# 3V3_LDO.net
KiCad netlist of a schematic drawn in Altium Designer
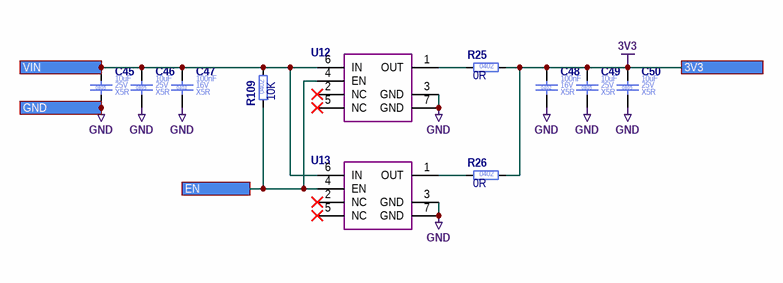
[diagram p0: 3V3_LDO.SchDoc]

(export (version "E")
  (design (tool "Eeschema 10.0.6"))
  (components
    (comp (ref "C45")
      (value "C_10UF_25V_X5R_0805_10")
      (footprint "C_0805_2012")
      (description "Ceramic Capacitor")
      (fields
        (field (name "CASE/PACKAGE") "0805")
        (field (name "VOLTAGE RATING (DC)") "25V")
        (field (name "DIELECTRIC") "X5R")
        (field (name "CAPACITANCE") "10uF")
        (field (name "TOLERANCE") "10%")
        (field (name "MANUFACTURER PART NUMBER") "CL21A106KAYNNNE")
      )
      (libsource (lib "7Sigma") (part "C"))
    )
    (comp (ref "C46")
      (value "C_10UF_25V_X5R_0805_10")
      (footprint "C_0805_2012")
      (description "Ceramic Capacitor")
      (fields
        (field (name "CASE/PACKAGE") "0805")
        (field (name "VOLTAGE RATING (DC)") "25V")
        (field (name "DIELECTRIC") "X5R")
        (field (name "CAPACITANCE") "10uF")
        (field (name "TOLERANCE") "10%")
        (field (name "MANUFACTURER PART NUMBER") "CL21A106KAYNNNE")
      )
      (libsource (lib "7Sigma") (part "C"))
    )
    (comp (ref "C47")
      (value "C_100NF_16V_X5R_0402_10")
      (footprint "C_0402_1005")
      (description "Ceramic Capacitor")
      (fields
        (field (name "CASE/PACKAGE") "0402")
        (field (name "VOLTAGE RATING (DC)") "16V")
        (field (name "DIELECTRIC") "X5R")
        (field (name "CAPACITANCE") "100nF")
        (field (name "TOLERANCE") "10%")
        (field (name "MANUFACTURER PART NUMBER") "EMK105BJ104KV-F")
      )
      (libsource (lib "7Sigma") (part "C"))
    )
    (comp (ref "C48")
      (value "C_100NF_16V_X5R_0402_10")
      (footprint "C_0402_1005")
      (description "Ceramic Capacitor")
      (fields
        (field (name "CASE/PACKAGE") "0402")
        (field (name "VOLTAGE RATING (DC)") "16V")
        (field (name "DIELECTRIC") "X5R")
        (field (name "CAPACITANCE") "100nF")
        (field (name "TOLERANCE") "10%")
        (field (name "MANUFACTURER PART NUMBER") "EMK105BJ104KV-F")
      )
      (libsource (lib "7Sigma") (part "C"))
    )
    (comp (ref "C49")
      (value "C_10UF_25V_X5R_0805_10")
      (footprint "C_0805_2012")
      (description "Ceramic Capacitor")
      (fields
        (field (name "CASE/PACKAGE") "0805")
        (field (name "VOLTAGE RATING (DC)") "25V")
        (field (name "DIELECTRIC") "X5R")
        (field (name "CAPACITANCE") "10uF")
        (field (name "TOLERANCE") "10%")
        (field (name "MANUFACTURER PART NUMBER") "CL21A106KAYNNNE")
      )
      (libsource (lib "7Sigma") (part "C"))
    )
    (comp (ref "C50")
      (value "C_10UF_25V_X5R_0805_10")
      (footprint "C_0805_2012")
      (description "Ceramic Capacitor")
      (fields
        (field (name "CASE/PACKAGE") "0805")
        (field (name "VOLTAGE RATING (DC)") "25V")
        (field (name "DIELECTRIC") "X5R")
        (field (name "CAPACITANCE") "10uF")
        (field (name "TOLERANCE") "10%")
        (field (name "MANUFACTURER PART NUMBER") "CL21A106KAYNNNE")
      )
      (libsource (lib "7Sigma") (part "C"))
    )
    (comp (ref "R25")
      (value "R_0R_0402_1")
      (footprint "R_0402_1005")
      (description "Thick Film Resistor")
      (fields
        (field (name "RESISTANCE") "0R")
        (field (name "CASE/PACKAGE") "0402")
        (field (name "TOLERANCE") "1%")
        (field (name "MANUFACTURER") "Yageo")
      )
      (libsource (lib "7Sigma") (part "R"))
    )
    (comp (ref "R26")
      (value "R_0R_0402_1")
      (footprint "R_0402_1005")
      (description "Thick Film Resistor")
      (fields
        (field (name "RESISTANCE") "0R")
        (field (name "CASE/PACKAGE") "0402")
        (field (name "TOLERANCE") "1%")
        (field (name "MANUFACTURER") "Yageo")
      )
      (libsource (lib "7Sigma") (part "R"))
    )
    (comp (ref "R109")
      (value "R_10K_0402_1")
      (footprint "R_0402_1005")
      (description "Thick Film Resistor")
      (fields
        (field (name "RESISTANCE") "10K")
        (field (name "CASE/PACKAGE") "0402")
        (field (name "TOLERANCE") "1%")
        (field (name "MANUFACTURER") "Yageo")
      )
      (libsource (lib "7Sigma") (part "R"))
    )
    (comp (ref "U12")
      (value "NCV8705MT33TCG")
      (footprint "WDFN6")
      (description "Low Dropout, Ultra-Low Iq, High PSRR, Ultra-Low Noise 3.3V")
      (fields (field (name "MANUFACTURER") "ON Semiconductor"))
      (libsource (lib "7Sigma") (part "NCV8705MT33TCG"))
    )
    (comp (ref "U13")
      (value "NCV8705MT33TCG")
      (footprint "WDFN6")
      (description "Low Dropout, Ultra-Low Iq, High PSRR, Ultra-Low Noise 3.3V")
      (fields (field (name "MANUFACTURER") "ON Semiconductor"))
      (libsource (lib "7Sigma") (part "NCV8705MT33TCG"))
    )
  )
  (nets
    (net (code "1") (name "/EN") (class "Default")
      (node (ref "R109") (pin "1") (pinfunction "1_1") (pintype "passive"))
      (node (ref "U12") (pin "4") (pinfunction "EN_4") (pintype "passive"))
      (node (ref "U13") (pin "4") (pinfunction "EN_4") (pintype "passive"))
    )
    (net (code "2") (name "/VIN") (class "Default")
      (node (ref "C45") (pin "1") (pinfunction "1_1") (pintype "passive"))
      (node (ref "C46") (pin "1") (pinfunction "1_1") (pintype "passive"))
      (node (ref "C47") (pin "1") (pinfunction "1_1") (pintype "passive"))
      (node (ref "R109") (pin "2") (pinfunction "2_2") (pintype "passive"))
      (node (ref "U12") (pin "6") (pinfunction "IN_6") (pintype "passive"))
      (node (ref "U13") (pin "6") (pinfunction "IN_6") (pintype "passive"))
    )
    (net (code "3") (name "3V3") (class "Default")
      (node (ref "C48") (pin "1") (pinfunction "1_1") (pintype "passive"))
      (node (ref "C49") (pin "1") (pinfunction "1_1") (pintype "passive"))
      (node (ref "C50") (pin "1") (pinfunction "1_1") (pintype "passive"))
      (node (ref "R25") (pin "2") (pinfunction "2_2") (pintype "passive"))
      (node (ref "R26") (pin "2") (pinfunction "2_2") (pintype "passive"))
    )
    (net (code "4") (name "GND") (class "Default")
      (node (ref "C45") (pin "2") (pinfunction "2_2") (pintype "passive"))
      (node (ref "C46") (pin "2") (pinfunction "2_2") (pintype "passive"))
      (node (ref "C47") (pin "2") (pinfunction "2_2") (pintype "passive"))
      (node (ref "C48") (pin "2") (pinfunction "2_2") (pintype "passive"))
      (node (ref "C49") (pin "2") (pinfunction "2_2") (pintype "passive"))
      (node (ref "C50") (pin "2") (pinfunction "2_2") (pintype "passive"))
      (node (ref "U12") (pin "3") (pinfunction "GND_3") (pintype "passive"))
      (node (ref "U12") (pin "7") (pinfunction "GND_7") (pintype "passive"))
      (node (ref "U13") (pin "3") (pinfunction "GND_3") (pintype "passive"))
      (node (ref "U13") (pin "7") (pinfunction "GND_7") (pintype "passive"))
    )
    (net (code "5") (name "Net-(U12-OUT)") (class "Default")
      (node (ref "R25") (pin "1") (pinfunction "1_1") (pintype "passive"))
      (node (ref "U12") (pin "1") (pinfunction "OUT_1") (pintype "passive"))
    )
    (net (code "6") (name "Net-(U13-OUT)") (class "Default")
      (node (ref "R26") (pin "1") (pinfunction "1_1") (pintype "passive"))
      (node (ref "U13") (pin "1") (pinfunction "OUT_1") (pintype "passive"))
    )
    (net (code "7") (name "unconnected-(U12-NC-Pad2)") (class "Default")
      (node (ref "U12") (pin "2") (pinfunction "NC_2") (pintype "passive+no_connect"))
    )
    (net (code "8") (name "unconnected-(U12-NC-Pad5)") (class "Default")
      (node (ref "U12") (pin "5") (pinfunction "NC_5") (pintype "passive+no_connect"))
    )
    (net (code "9") (name "unconnected-(U13-NC-Pad2)") (class "Default")
      (node (ref "U13") (pin "2") (pinfunction "NC_2") (pintype "passive+no_connect"))
    )
    (net (code "10") (name "unconnected-(U13-NC-Pad5)") (class "Default")
      (node (ref "U13") (pin "5") (pinfunction "NC_5") (pintype "passive+no_connect"))
    )
  )
)
